# coreboards_mod001_rp2350_v01.net
KiCad netlist of a schematic drawn in EasyEDA Pro
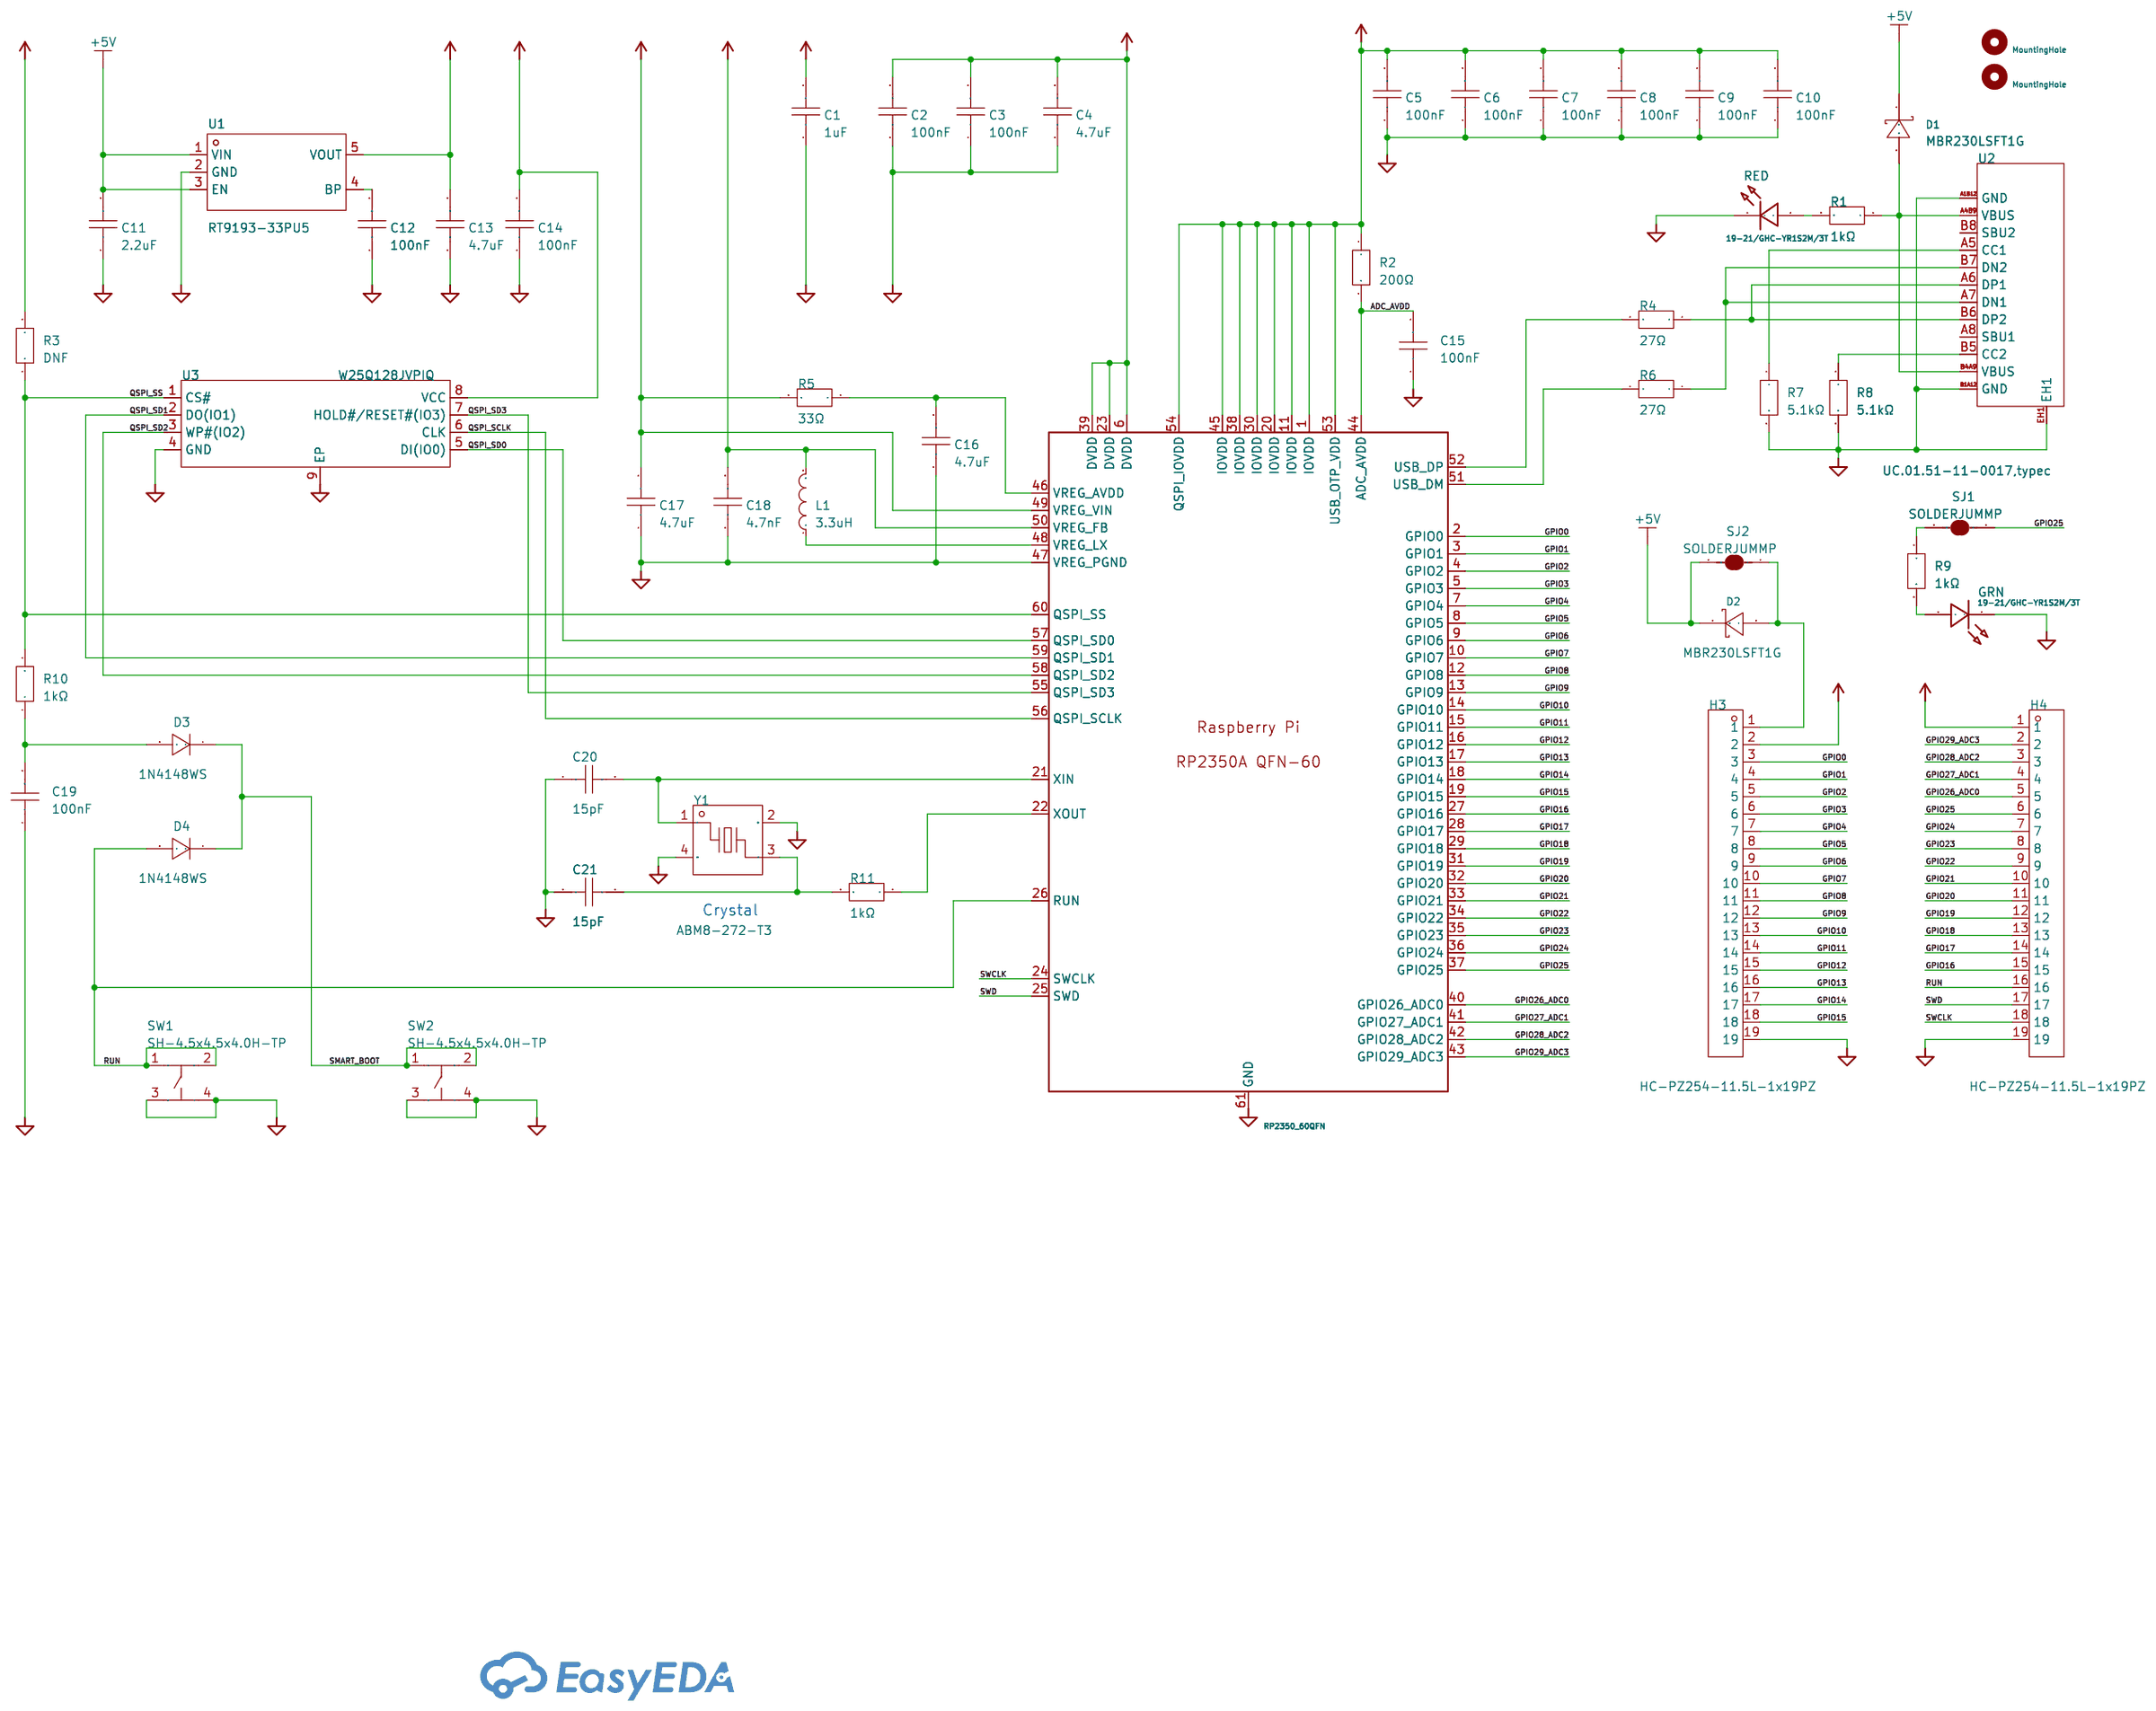
[diagram p0: schematic sheet]

(export (version "E")
  (design (tool "Eeschema 10.0.6"))
  (components
    (comp (ref "C1")
      (value "1uF")
      (footprint "easyedapro:C0603")
      (description "Capacitance:1nF Tolerance:±5% Tolerance:±5% Voltage Rating:200V Temperature Coefficient:C0G")
      (fields
        (field (name "Manufacturer Part") "C0603C102J2GECAUTO")
        (field (name "Manufacturer") "KEMET(基美)")
      )
      (libsource (lib "easyedapro") (part "C0603C102J2GECAUTO"))
    )
    (comp (ref "C2")
      (value "100nF")
      (footprint "easyedapro:C0603")
      (description "Capacitance:1nF Tolerance:±5% Tolerance:±5% Voltage Rating:200V Temperature Coefficient:C0G")
      (fields
        (field (name "Manufacturer Part") "C0603C102J2GECAUTO")
        (field (name "Manufacturer") "KEMET(基美)")
      )
      (libsource (lib "easyedapro") (part "C0603C102J2GECAUTO"))
    )
    (comp (ref "C3")
      (value "100nF")
      (footprint "easyedapro:C0603")
      (description "Capacitance:1nF Tolerance:±5% Tolerance:±5% Voltage Rating:200V Temperature Coefficient:C0G")
      (fields
        (field (name "Manufacturer Part") "C0603C102J2GECAUTO")
        (field (name "Manufacturer") "KEMET(基美)")
      )
      (libsource (lib "easyedapro") (part "C0603C102J2GECAUTO"))
    )
    (comp (ref "C4")
      (value "4.7uF")
      (footprint "easyedapro:C0603")
      (description "Capacitance:1nF Tolerance:±5% Tolerance:±5% Voltage Rating:200V Temperature Coefficient:C0G")
      (fields
        (field (name "Manufacturer Part") "C0603C102J2GECAUTO")
        (field (name "Manufacturer") "KEMET(基美)")
      )
      (libsource (lib "easyedapro") (part "C0603C102J2GECAUTO"))
    )
    (comp (ref "C5")
      (value "100nF")
      (footprint "easyedapro:C0603")
      (description "Capacitance:1nF Tolerance:±5% Tolerance:±5% Voltage Rating:200V Temperature Coefficient:C0G")
      (fields
        (field (name "Manufacturer Part") "C0603C102J2GECAUTO")
        (field (name "Manufacturer") "KEMET(基美)")
      )
      (libsource (lib "easyedapro") (part "C0603C102J2GECAUTO"))
    )
    (comp (ref "C6")
      (value "100nF")
      (footprint "easyedapro:C0603")
      (description "Capacitance:1nF Tolerance:±5% Tolerance:±5% Voltage Rating:200V Temperature Coefficient:C0G")
      (fields
        (field (name "Manufacturer Part") "C0603C102J2GECAUTO")
        (field (name "Manufacturer") "KEMET(基美)")
      )
      (libsource (lib "easyedapro") (part "C0603C102J2GECAUTO"))
    )
    (comp (ref "C7")
      (value "100nF")
      (footprint "easyedapro:C0603")
      (description "Capacitance:1nF Tolerance:±5% Tolerance:±5% Voltage Rating:200V Temperature Coefficient:C0G")
      (fields
        (field (name "Manufacturer Part") "C0603C102J2GECAUTO")
        (field (name "Manufacturer") "KEMET(基美)")
      )
      (libsource (lib "easyedapro") (part "C0603C102J2GECAUTO"))
    )
    (comp (ref "C8")
      (value "100nF")
      (footprint "easyedapro:C0603")
      (description "Capacitance:1nF Tolerance:±5% Tolerance:±5% Voltage Rating:200V Temperature Coefficient:C0G")
      (fields
        (field (name "Manufacturer Part") "C0603C102J2GECAUTO")
        (field (name "Manufacturer") "KEMET(基美)")
      )
      (libsource (lib "easyedapro") (part "C0603C102J2GECAUTO"))
    )
    (comp (ref "C9")
      (value "100nF")
      (footprint "easyedapro:C0603")
      (description "Capacitance:1nF Tolerance:±5% Tolerance:±5% Voltage Rating:200V Temperature Coefficient:C0G")
      (fields
        (field (name "Manufacturer Part") "C0603C102J2GECAUTO")
        (field (name "Manufacturer") "KEMET(基美)")
      )
      (libsource (lib "easyedapro") (part "C0603C102J2GECAUTO"))
    )
    (comp (ref "C10")
      (value "100nF")
      (footprint "easyedapro:C0603")
      (description "Capacitance:1nF Tolerance:±5% Tolerance:±5% Voltage Rating:200V Temperature Coefficient:C0G")
      (fields
        (field (name "Manufacturer Part") "C0603C102J2GECAUTO")
        (field (name "Manufacturer") "KEMET(基美)")
      )
      (libsource (lib "easyedapro") (part "C0603C102J2GECAUTO"))
    )
    (comp (ref "C11")
      (value "2.2uF")
      (footprint "easyedapro:C0603")
      (description "Capacitance:1nF Tolerance:±5% Tolerance:±5% Voltage Rating:200V Temperature Coefficient:C0G")
      (fields
        (field (name "Manufacturer Part") "C0603C102J2GECAUTO")
        (field (name "Manufacturer") "KEMET(基美)")
      )
      (libsource (lib "easyedapro") (part "C0603C102J2GECAUTO"))
    )
    (comp (ref "C12")
      (value "100nF")
      (footprint "easyedapro:C0603")
      (description "Capacitance:1nF Tolerance:±5% Tolerance:±5% Voltage Rating:200V Temperature Coefficient:C0G")
      (fields
        (field (name "Manufacturer Part") "C0603C102J2GECAUTO")
        (field (name "Manufacturer") "KEMET(基美)")
      )
      (libsource (lib "easyedapro") (part "C0603C102J2GECAUTO"))
    )
    (comp (ref "C13")
      (value "4.7uF")
      (footprint "easyedapro:C0603")
      (description "Capacitance:1nF Tolerance:±5% Tolerance:±5% Voltage Rating:200V Temperature Coefficient:C0G")
      (fields
        (field (name "Manufacturer Part") "C0603C102J2GECAUTO")
        (field (name "Manufacturer") "KEMET(基美)")
      )
      (libsource (lib "easyedapro") (part "C0603C102J2GECAUTO"))
    )
    (comp (ref "C14")
      (value "100nF")
      (footprint "easyedapro:C0603")
      (description "Capacitance:1nF Tolerance:±5% Tolerance:±5% Voltage Rating:200V Temperature Coefficient:C0G")
      (fields
        (field (name "Manufacturer Part") "C0603C102J2GECAUTO")
        (field (name "Manufacturer") "KEMET(基美)")
      )
      (libsource (lib "easyedapro") (part "C0603C102J2GECAUTO"))
    )
    (comp (ref "C15")
      (value "100nF")
      (footprint "easyedapro:C0603")
      (description "Capacitance:1nF Tolerance:±5% Tolerance:±5% Voltage Rating:200V Temperature Coefficient:C0G")
      (fields
        (field (name "Manufacturer Part") "C0603C102J2GECAUTO")
        (field (name "Manufacturer") "KEMET(基美)")
      )
      (libsource (lib "easyedapro") (part "C0603C102J2GECAUTO"))
    )
    (comp (ref "C16")
      (value "4.7uF")
      (footprint "easyedapro:C0603")
      (description "Capacitance:1nF Tolerance:±5% Tolerance:±5% Voltage Rating:200V Temperature Coefficient:C0G")
      (fields
        (field (name "Manufacturer Part") "C0603C102J2GECAUTO")
        (field (name "Manufacturer") "KEMET(基美)")
      )
      (libsource (lib "easyedapro") (part "C0603C102J2GECAUTO"))
    )
    (comp (ref "C17")
      (value "4.7uF")
      (footprint "easyedapro:C0603")
      (description "Capacitance:1nF Tolerance:±5% Tolerance:±5% Voltage Rating:200V Temperature Coefficient:C0G")
      (fields
        (field (name "Manufacturer Part") "C0603C102J2GECAUTO")
        (field (name "Manufacturer") "KEMET(基美)")
      )
      (libsource (lib "easyedapro") (part "C0603C102J2GECAUTO"))
    )
    (comp (ref "C18")
      (value "4.7nF")
      (footprint "easyedapro:C0603")
      (description "Capacitance:1nF Tolerance:±5% Tolerance:±5% Voltage Rating:200V Temperature Coefficient:C0G")
      (fields
        (field (name "Manufacturer Part") "C0603C102J2GECAUTO")
        (field (name "Manufacturer") "KEMET(基美)")
      )
      (libsource (lib "easyedapro") (part "C0603C102J2GECAUTO"))
    )
    (comp (ref "C19")
      (value "100nF")
      (footprint "easyedapro:C0603")
      (description "Capacitance:1nF Tolerance:±5% Tolerance:±5% Voltage Rating:200V Temperature Coefficient:C0G")
      (fields
        (field (name "Manufacturer Part") "C0603C102J2GECAUTO")
        (field (name "Manufacturer") "KEMET(基美)")
      )
      (libsource (lib "easyedapro") (part "C0603C102J2GECAUTO"))
    )
    (comp (ref "C20")
      (value "15pF")
      (footprint "easyedapro:C0603")
      (description "Capacitance:1nF Tolerance:±5% Tolerance:±5% Voltage Rating:200V Temperature Coefficient:C0G")
      (fields
        (field (name "Manufacturer Part") "C0603C102J2GECAUTO")
        (field (name "Manufacturer") "KEMET(基美)")
      )
      (libsource (lib "easyedapro") (part "C0603C102J2GECAUTO"))
    )
    (comp (ref "C21")
      (value "15pF")
      (footprint "easyedapro:C0603")
      (description "Capacitance:1nF Tolerance:±5% Tolerance:±5% Voltage Rating:200V Temperature Coefficient:C0G")
      (fields
        (field (name "Manufacturer Part") "C0603C102J2GECAUTO")
        (field (name "Manufacturer") "KEMET(基美)")
      )
      (libsource (lib "easyedapro") (part "C0603C102J2GECAUTO"))
    )
    (comp (ref "D1")
      (value "MBR230LSFT1G")
      (footprint "easyedapro:SOD-123FL_L2.7-W1.8-LS3.8-RD")
      (fields (field (name "Manufacturer") "onsemi(安森美)"))
      (libsource (lib "easyedapro") (part "MBR230LSFT1G"))
    )
    (comp (ref "D2")
      (value "MBR230LSFT1G")
      (footprint "easyedapro:SOD-123FL_L2.7-W1.8-LS3.8-RD")
      (fields (field (name "Manufacturer") "onsemi(安森美)"))
      (libsource (lib "easyedapro") (part "MBR230LSFT1G"))
    )
    (comp (ref "D3")
      (value "1N4148WS")
      (footprint "easyedapro:SOD-323_L1.8-W1.3-LS2.5-RD")
      (fields (field (name "Manufacturer") "CJ(江苏长电/长晶)"))
      (libsource (lib "easyedapro") (part "1N4148WS T4"))
    )
    (comp (ref "D4")
      (value "1N4148WS")
      (footprint "easyedapro:SOD-323_L1.8-W1.3-LS2.5-RD")
      (fields (field (name "Manufacturer") "CJ(江苏长电/长晶)"))
      (libsource (lib "easyedapro") (part "1N4148WS T4"))
    )
    (comp (ref "GRN")
      (value "19-21/GHC-YR1S2M/3T")
      (footprint "easyedapro:LED-SMD_L1.6-W0.8-RD")
      (fields (field (name "Manufacturer") "EVERLIGHT(亿光)") (field (name "Contributor") "LCSC"))
      (libsource (lib "easyedapro") (part "19-21/GHC-YR1S2M/3T"))
    )
    (comp (ref "H1")
      (value "MountingHole")
      (footprint "easyedapro:MountingHole:MountingHole_2.7mm_M2.5")
      (libsource (lib "easyedapro") (part "Mechanical_MountingHole"))
    )
    (comp (ref "H2")
      (value "MountingHole")
      (footprint "easyedapro:MountingHole:MountingHole_2.7mm_M2.5")
      (libsource (lib "easyedapro") (part "Mechanical_MountingHole"))
    )
    (comp (ref "H3")
      (value "HC-PZ254-11.5L-1x19PZ")
      (footprint "easyedapro:HDR-TH_19P-P2.54-V-M")
      (fields (field (name "Manufacturer") "HC(虹成电子)"))
      (libsource (lib "easyedapro") (part "HC-PZ254-11.5L-1X19PZ"))
    )
    (comp (ref "H4")
      (value "HC-PZ254-11.5L-1x19PZ")
      (footprint "easyedapro:HDR-TH_19P-P2.54-V-M")
      (fields (field (name "Manufacturer") "HC(虹成电子)"))
      (libsource (lib "easyedapro") (part "HC-PZ254-11.5L-1X19PZ"))
    )
    (comp (ref "L1")
      (value "3.3uH")
      (footprint "easyedapro:IND-SMD_L2.0-W1.6_AOTA-B201610S3R3-101-T")
      (fields
        (field (name "Manufacturer Part") "AOTA-B201610S3R3-101-T")
        (field (name "Manufacturer") "ABRACON")
      )
      (libsource (lib "easyedapro") (part "AOTA-B201610S3R3-101-T"))
    )
    (comp (ref "R1")
      (value "1kΩ")
      (footprint "easyedapro:R0603")
      (fields (field (name "Manufacturer Part") "RCC06031K50FKEA") (field (name "Manufacturer") "VISHAY(威世)"))
      (libsource (lib "easyedapro") (part "RCC06031K50FKEA"))
    )
    (comp (ref "R2")
      (value "200Ω")
      (footprint "easyedapro:R0603")
      (fields (field (name "Manufacturer Part") "RCC06031K50FKEA") (field (name "Manufacturer") "VISHAY(威世)"))
      (libsource (lib "easyedapro") (part "RCC06031K50FKEA"))
    )
    (comp (ref "R3")
      (value "DNF")
      (footprint "easyedapro:R0603")
      (fields (field (name "Manufacturer Part") "RCC06031K50FKEA") (field (name "Manufacturer") "VISHAY(威世)"))
      (libsource (lib "easyedapro") (part "RCC06031K50FKEA"))
    )
    (comp (ref "R4")
      (value "27Ω")
      (footprint "easyedapro:R0603")
      (fields (field (name "Manufacturer Part") "RCC06031K50FKEA") (field (name "Manufacturer") "VISHAY(威世)"))
      (libsource (lib "easyedapro") (part "RCC06031K50FKEA"))
    )
    (comp (ref "R5")
      (value "33Ω")
      (footprint "easyedapro:R0603")
      (fields (field (name "Manufacturer Part") "RCC06031K50FKEA") (field (name "Manufacturer") "VISHAY(威世)"))
      (libsource (lib "easyedapro") (part "RCC06031K50FKEA"))
    )
    (comp (ref "R6")
      (value "27Ω")
      (footprint "easyedapro:R0603")
      (fields (field (name "Manufacturer Part") "RCC06031K50FKEA") (field (name "Manufacturer") "VISHAY(威世)"))
      (libsource (lib "easyedapro") (part "RCC06031K50FKEA"))
    )
    (comp (ref "R7")
      (value "5.1kΩ")
      (footprint "easyedapro:R0603")
      (fields (field (name "Manufacturer Part") "RCC06031K50FKEA") (field (name "Manufacturer") "VISHAY(威世)"))
      (libsource (lib "easyedapro") (part "RCC06031K50FKEA"))
    )
    (comp (ref "R8")
      (value "5.1kΩ")
      (footprint "easyedapro:R0603")
      (fields (field (name "Manufacturer Part") "RCC06031K50FKEA") (field (name "Manufacturer") "VISHAY(威世)"))
      (libsource (lib "easyedapro") (part "RCC06031K50FKEA"))
    )
    (comp (ref "R9")
      (value "1kΩ")
      (footprint "easyedapro:R0603")
      (fields (field (name "Manufacturer Part") "RCC06031K50FKEA") (field (name "Manufacturer") "VISHAY(威世)"))
      (libsource (lib "easyedapro") (part "RCC06031K50FKEA"))
    )
    (comp (ref "R10")
      (value "1kΩ")
      (footprint "easyedapro:R0603")
      (fields (field (name "Manufacturer Part") "RCC06031K50FKEA") (field (name "Manufacturer") "VISHAY(威世)"))
      (libsource (lib "easyedapro") (part "RCC06031K50FKEA"))
    )
    (comp (ref "R11")
      (value "1kΩ")
      (footprint "easyedapro:R0603")
      (fields (field (name "Manufacturer Part") "RCC06031K50FKEA") (field (name "Manufacturer") "VISHAY(威世)"))
      (libsource (lib "easyedapro") (part "RCC06031K50FKEA"))
    )
    (comp (ref "RED")
      (value "19-21/GHC-YR1S2M/3T")
      (footprint "easyedapro:LED-SMD_L1.6-W0.8-RD")
      (fields (field (name "Manufacturer") "EVERLIGHT(亿光)") (field (name "Contributor") "LCSC"))
      (libsource (lib "easyedapro") (part "19-21/GHC-YR1S2M/3T"))
    )
    (comp (ref "SJ1")
      (value "SOLDERJUMMP")
      (footprint "easyedapro:SJ_2S-NO")
      (fields (field (name "Contributor") "SparkFun"))
      (libsource (lib "easyedapro") (part "SOLDERJUMPERNO"))
    )
    (comp (ref "SJ2")
      (value "SOLDERJUMMP")
      (footprint "easyedapro:SJ_2S-NO")
      (fields (field (name "Contributor") "SparkFun"))
      (libsource (lib "easyedapro") (part "SOLDERJUMPERNO"))
    )
    (comp (ref "SW1")
      (value "SH-4.5x4.5x4.0H-TP")
      (footprint "easyedapro:SW-SMD_4P-SH-4.5X4.5X4.0H-TP")
      (fields (field (name "Manufacturer") "SHOU HAN(首韩)"))
      (libsource (lib "easyedapro") (part "SH-4.5X4.5X4.0H-TP"))
    )
    (comp (ref "SW2")
      (value "SH-4.5x4.5x4.0H-TP")
      (footprint "easyedapro:SW-SMD_4P-SH-4.5X4.5X4.0H-TP")
      (fields (field (name "Manufacturer") "SHOU HAN(首韩)"))
      (libsource (lib "easyedapro") (part "SH-4.5X4.5X4.0H-TP"))
    )
    (comp (ref "U1")
      (value "RT9193-33PU5")
      (footprint "easyedapro:SC-70-5_L2.0-W1.3-P0.65-LS2.1-BL")
      (description "Output Type:-")
      (libsource (lib "easyedapro") (part "RT9193-33PU5"))
    )
    (comp (ref "U2")
      (value "UC.01.51-11-0017,typec")
      (footprint "easyedapro:TYPE-C-SMD_UC.01.51-11-0017")
      (libsource (lib "easyedapro") (part "UC.01.51-11-0017,TYPEC"))
    )
    (comp (ref "U3")
      (value "W25Q128JVPIQ")
      (footprint "easyedapro:WSON-8_L5.0-W6.0-P1.27-BL-EP")
      (fields (field (name "Manufacturer") "Winbond(华邦)"))
      (libsource (lib "easyedapro") (part "W25Q128JVPIQ"))
    )
    (comp (ref "U4")
      (value "RP2350_60QFN")
      (footprint "easyedapro:RP2350_60QFN_minimal:RP2350-QFN-60-1EP_7x7_P0.4mm_EP3.4x3.4mm_ThermalVias")
      (libsource (lib "easyedapro") (part "MCU_RaspberryPi_RP2350_RP2350_60QFN"))
    )
    (comp (ref "Y1")
      (value "ABM8-272-T3")
      (footprint "easyedapro:CRYSTAL-SMD_4P-L3.2-W2.5-BL-2")
      (libsource (lib "easyedapro") (part "ABM8-272-T3"))
    )
  )
  (nets
    (net (code "1") (name "+5V") (class "Default")
      (node (ref "C11") (pin "2") (pinfunction "2_2") (pintype "unspecified"))
      (node (ref "D1") (pin "1") (pinfunction "C_1") (pintype "input"))
      (node (ref "D2") (pin "1") (pinfunction "C_1") (pintype "input"))
      (node (ref "SJ2") (pin "2") (pinfunction "2_2") (pintype "unspecified"))
      (node (ref "U1") (pin "1") (pinfunction "VIN_1") (pintype "unspecified"))
      (node (ref "U1") (pin "3") (pinfunction "EN_3") (pintype "unspecified"))
    )
    (net (code "2") (name "/ADC_AVDD") (class "Default")
      (node (ref "C15") (pin "2") (pinfunction "2_2") (pintype "unspecified"))
      (node (ref "R2") (pin "2") (pinfunction "2_2") (pintype "unspecified"))
      (node (ref "U4") (pin "44") (pinfunction "ADC_AVDD_44") (pintype "unspecified"))
    )
    (net (code "3") (name "/GPIO0") (class "Default")
      (node (ref "H3") (pin "3") (pinfunction "3_3") (pintype "unspecified"))
      (node (ref "U4") (pin "2") (pinfunction "GPIO0_2") (pintype "bidirectional"))
    )
    (net (code "4") (name "/GPIO1") (class "Default")
      (node (ref "H3") (pin "4") (pinfunction "4_4") (pintype "unspecified"))
      (node (ref "U4") (pin "3") (pinfunction "GPIO1_3") (pintype "bidirectional"))
    )
    (net (code "5") (name "/GPIO2") (class "Default")
      (node (ref "H3") (pin "5") (pinfunction "5_5") (pintype "unspecified"))
      (node (ref "U4") (pin "4") (pinfunction "GPIO2_4") (pintype "bidirectional"))
    )
    (net (code "6") (name "/GPIO3") (class "Default")
      (node (ref "H3") (pin "6") (pinfunction "6_6") (pintype "unspecified"))
      (node (ref "U4") (pin "5") (pinfunction "GPIO3_5") (pintype "bidirectional"))
    )
    (net (code "7") (name "/GPIO4") (class "Default")
      (node (ref "H3") (pin "7") (pinfunction "7_7") (pintype "unspecified"))
      (node (ref "U4") (pin "7") (pinfunction "GPIO4_7") (pintype "bidirectional"))
    )
    (net (code "8") (name "/GPIO5") (class "Default")
      (node (ref "H3") (pin "8") (pinfunction "8_8") (pintype "unspecified"))
      (node (ref "U4") (pin "8") (pinfunction "GPIO5_8") (pintype "bidirectional"))
    )
    (net (code "9") (name "/GPIO6") (class "Default")
      (node (ref "H3") (pin "9") (pinfunction "9_9") (pintype "unspecified"))
      (node (ref "U4") (pin "9") (pinfunction "GPIO6_9") (pintype "bidirectional"))
    )
    (net (code "10") (name "/GPIO7") (class "Default")
      (node (ref "H3") (pin "10") (pinfunction "10_10") (pintype "unspecified"))
      (node (ref "U4") (pin "10") (pinfunction "GPIO7_10") (pintype "bidirectional"))
    )
    (net (code "11") (name "/GPIO8") (class "Default")
      (node (ref "H3") (pin "11") (pinfunction "11_11") (pintype "unspecified"))
      (node (ref "U4") (pin "12") (pinfunction "GPIO8_12") (pintype "bidirectional"))
    )
    (net (code "12") (name "/GPIO9") (class "Default")
      (node (ref "H3") (pin "12") (pinfunction "12_12") (pintype "unspecified"))
      (node (ref "U4") (pin "13") (pinfunction "GPIO9_13") (pintype "bidirectional"))
    )
    (net (code "13") (name "/GPIO10") (class "Default")
      (node (ref "H3") (pin "13") (pinfunction "13_13") (pintype "unspecified"))
      (node (ref "U4") (pin "14") (pinfunction "GPIO10_14") (pintype "bidirectional"))
    )
    (net (code "14") (name "/GPIO11") (class "Default")
      (node (ref "H3") (pin "14") (pinfunction "14_14") (pintype "unspecified"))
      (node (ref "U4") (pin "15") (pinfunction "GPIO11_15") (pintype "bidirectional"))
    )
    (net (code "15") (name "/GPIO12") (class "Default")
      (node (ref "H3") (pin "15") (pinfunction "15_15") (pintype "unspecified"))
      (node (ref "U4") (pin "16") (pinfunction "GPIO12_16") (pintype "bidirectional"))
    )
    (net (code "16") (name "/GPIO13") (class "Default")
      (node (ref "H3") (pin "16") (pinfunction "16_16") (pintype "unspecified"))
      (node (ref "U4") (pin "17") (pinfunction "GPIO13_17") (pintype "bidirectional"))
    )
    (net (code "17") (name "/GPIO14") (class "Default")
      (node (ref "H3") (pin "17") (pinfunction "17_17") (pintype "unspecified"))
      (node (ref "U4") (pin "18") (pinfunction "GPIO14_18") (pintype "bidirectional"))
    )
    (net (code "18") (name "/GPIO15") (class "Default")
      (node (ref "H3") (pin "18") (pinfunction "18_18") (pintype "unspecified"))
      (node (ref "U4") (pin "19") (pinfunction "GPIO15_19") (pintype "bidirectional"))
    )
    (net (code "19") (name "/GPIO16") (class "Default")
      (node (ref "H4") (pin "15") (pinfunction "15_15") (pintype "unspecified"))
      (node (ref "U4") (pin "27") (pinfunction "GPIO16_27") (pintype "bidirectional"))
    )
    (net (code "20") (name "/GPIO17") (class "Default")
      (node (ref "H4") (pin "14") (pinfunction "14_14") (pintype "unspecified"))
      (node (ref "U4") (pin "28") (pinfunction "GPIO17_28") (pintype "bidirectional"))
    )
    (net (code "21") (name "/GPIO18") (class "Default")
      (node (ref "H4") (pin "13") (pinfunction "13_13") (pintype "unspecified"))
      (node (ref "U4") (pin "29") (pinfunction "GPIO18_29") (pintype "bidirectional"))
    )
    (net (code "22") (name "/GPIO19") (class "Default")
      (node (ref "H4") (pin "12") (pinfunction "12_12") (pintype "unspecified"))
      (node (ref "U4") (pin "31") (pinfunction "GPIO19_31") (pintype "bidirectional"))
    )
    (net (code "23") (name "/GPIO20") (class "Default")
      (node (ref "H4") (pin "11") (pinfunction "11_11") (pintype "unspecified"))
      (node (ref "U4") (pin "32") (pinfunction "GPIO20_32") (pintype "bidirectional"))
    )
    (net (code "24") (name "/GPIO21") (class "Default")
      (node (ref "H4") (pin "10") (pinfunction "10_10") (pintype "unspecified"))
      (node (ref "U4") (pin "33") (pinfunction "GPIO21_33") (pintype "bidirectional"))
    )
    (net (code "25") (name "/GPIO22") (class "Default")
      (node (ref "H4") (pin "9") (pinfunction "9_9") (pintype "unspecified"))
      (node (ref "U4") (pin "34") (pinfunction "GPIO22_34") (pintype "bidirectional"))
    )
    (net (code "26") (name "/GPIO23") (class "Default")
      (node (ref "H4") (pin "8") (pinfunction "8_8") (pintype "unspecified"))
      (node (ref "U4") (pin "35") (pinfunction "GPIO23_35") (pintype "bidirectional"))
    )
    (net (code "27") (name "/GPIO24") (class "Default")
      (node (ref "H4") (pin "7") (pinfunction "7_7") (pintype "unspecified"))
      (node (ref "U4") (pin "36") (pinfunction "GPIO24_36") (pintype "bidirectional"))
    )
    (net (code "28") (name "/GPIO25") (class "Default")
      (node (ref "H4") (pin "6") (pinfunction "6_6") (pintype "unspecified"))
      (node (ref "SJ1") (pin "1") (pinfunction "1_1") (pintype "unspecified"))
      (node (ref "U4") (pin "37") (pinfunction "GPIO25_37") (pintype "bidirectional"))
    )
    (net (code "29") (name "/GPIO26_ADC0") (class "Default")
      (node (ref "H4") (pin "5") (pinfunction "5_5") (pintype "unspecified"))
      (node (ref "U4") (pin "40") (pinfunction "GPIO26_ADC0_40") (pintype "bidirectional"))
    )
    (net (code "30") (name "/GPIO27_ADC1") (class "Default")
      (node (ref "H4") (pin "4") (pinfunction "4_4") (pintype "unspecified"))
      (node (ref "U4") (pin "41") (pinfunction "GPIO27_ADC1_41") (pintype "bidirectional"))
    )
    (net (code "31") (name "/GPIO28_ADC2") (class "Default")
      (node (ref "H4") (pin "3") (pinfunction "3_3") (pintype "unspecified"))
      (node (ref "U4") (pin "42") (pinfunction "GPIO28_ADC2_42") (pintype "bidirectional"))
    )
    (net (code "32") (name "/GPIO29_ADC3") (class "Default")
      (node (ref "H4") (pin "2") (pinfunction "2_2") (pintype "unspecified"))
      (node (ref "U4") (pin "43") (pinfunction "GPIO29_ADC3_43") (pintype "bidirectional"))
    )
    (net (code "33") (name "/QSPI_SCLK") (class "Default")
      (node (ref "U3") (pin "6") (pinfunction "CLK_6") (pintype "unspecified"))
      (node (ref "U4") (pin "56") (pinfunction "QSPI_SCLK_56") (pintype "output"))
    )
    (net (code "34") (name "/QSPI_SD0") (class "Default")
      (node (ref "U3") (pin "5") (pinfunction "DI(IO0)_5") (pintype "unspecified"))
      (node (ref "U4") (pin "57") (pinfunction "QSPI_SD0_57") (pintype "bidirectional"))
    )
    (net (code "35") (name "/QSPI_SD1") (class "Default")
      (node (ref "U3") (pin "2") (pinfunction "DO(IO1)_2") (pintype "unspecified"))
      (node (ref "U4") (pin "59") (pinfunction "QSPI_SD1_59") (pintype "bidirectional"))
    )
    (net (code "36") (name "/QSPI_SD2") (class "Default")
      (node (ref "U3") (pin "3") (pinfunction "WP#(IO2)_3") (pintype "unspecified"))
      (node (ref "U4") (pin "58") (pinfunction "QSPI_SD2_58") (pintype "bidirectional"))
    )
    (net (code "37") (name "/QSPI_SD3") (class "Default")
      (node (ref "U3") (pin "7") (pinfunction "HOLD#/RESET#(IO3)_7") (pintype "unspecified"))
      (node (ref "U4") (pin "55") (pinfunction "QSPI_SD3_55") (pintype "bidirectional"))
    )
    (net (code "38") (name "/QSPI_SS") (class "Default")
      (node (ref "R10") (pin "2") (pinfunction "2_2") (pintype "unspecified"))
      (node (ref "R3") (pin "1") (pinfunction "1_1") (pintype "unspecified"))
      (node (ref "U3") (pin "1") (pinfunction "CS#_1") (pintype "unspecified"))
      (node (ref "U4") (pin "60") (pinfunction "QSPI_SS_60") (pintype "bidirectional"))
    )
    (net (code "39") (name "/RUN") (class "Default")
      (node (ref "D4") (pin "2") (pinfunction "A_2") (pintype "unspecified"))
      (node (ref "H4") (pin "16") (pinfunction "16_16") (pintype "unspecified"))
      (node (ref "SW1") (pin "1") (pinfunction "1_1") (pintype "unspecified"))
      (node (ref "SW1") (pin "2") (pinfunction "2_2") (pintype "unspecified"))
      (node (ref "U4") (pin "26") (pinfunction "RUN_26") (pintype "input"))
    )
    (net (code "40") (name "/SMART_BOOT") (class "Default")
      (node (ref "D3") (pin "1") (pinfunction "K_1") (pintype "unspecified"))
      (node (ref "D4") (pin "1") (pinfunction "K_1") (pintype "unspecified"))
      (node (ref "SW2") (pin "1") (pinfunction "1_1") (pintype "unspecified"))
      (node (ref "SW2") (pin "2") (pinfunction "2_2") (pintype "unspecified"))
    )
    (net (code "41") (name "/SWCLK") (class "Default")
      (node (ref "H4") (pin "18") (pinfunction "18_18") (pintype "unspecified"))
      (node (ref "U4") (pin "24") (pinfunction "SWCLK_24") (pintype "output"))
    )
    (net (code "42") (name "/SWD") (class "Default")
      (node (ref "H4") (pin "17") (pinfunction "17_17") (pintype "unspecified"))
      (node (ref "U4") (pin "25") (pinfunction "SWD_25") (pintype "bidirectional"))
    )
    (net (code "43") (name "Net-(C21-Pad2)") (class "Default")
      (node (ref "C21") (pin "2") (pinfunction "2_2") (pintype "unspecified"))
      (node (ref "R11") (pin "2") (pinfunction "2_2") (pintype "unspecified"))
      (node (ref "Y1") (pin "3") (pinfunction "3_3") (pintype "input"))
    )
    (net (code "44") (name "Net-(D1-A)") (class "Default")
      (node (ref "D1") (pin "2") (pinfunction "A_2") (pintype "input"))
      (node (ref "R1") (pin "1") (pinfunction "1_1") (pintype "unspecified"))
      (node (ref "U2") (pin "A4B9") (pinfunction "VBUS_A4B9") (pintype "unspecified"))
      (node (ref "U2") (pin "B4A9") (pinfunction "VBUS_B4A9") (pintype "unspecified"))
    )
    (net (code "45") (name "Net-(D2-A)") (class "Default")
      (node (ref "D2") (pin "2") (pinfunction "A_2") (pintype "input"))
      (node (ref "H3") (pin "1") (pinfunction "1_1") (pintype "unspecified"))
      (node (ref "SJ2") (pin "1") (pinfunction "1_1") (pintype "unspecified"))
    )
    (net (code "46") (name "Net-(D3-A)") (class "Default")
      (node (ref "C19") (pin "2") (pinfunction "2_2") (pintype "unspecified"))
      (node (ref "D3") (pin "2") (pinfunction "A_2") (pintype "unspecified"))
      (node (ref "R10") (pin "1") (pinfunction "1_1") (pintype "unspecified"))
    )
    (net (code "47") (name "Net-(GRN-+)") (class "Default")
      (node (ref "GRN") (pin "2") (pinfunction "+_2") (pintype "unspecified"))
      (node (ref "R9") (pin "2") (pinfunction "2_2") (pintype "unspecified"))
    )
    (net (code "48") (name "Net-(R9-Pad1)") (class "Default")
      (node (ref "R9") (pin "1") (pinfunction "1_1") (pintype "unspecified"))
      (node (ref "SJ1") (pin "2") (pinfunction "2_2") (pintype "unspecified"))
    )
    (net (code "49") (name "Net-(RED-+)") (class "Default")
      (node (ref "R1") (pin "2") (pinfunction "2_2") (pintype "unspecified"))
      (node (ref "RED") (pin "2") (pinfunction "+_2") (pintype "unspecified"))
    )
    (net (code "50") (name "Net-(U1-BP)") (class "Default")
      (node (ref "C12") (pin "2") (pinfunction "2_2") (pintype "unspecified"))
      (node (ref "U1") (pin "4") (pinfunction "BP_4") (pintype "unspecified"))
    )
    (net (code "51") (name "Net-(U2-CC1)") (class "Default")
      (node (ref "R7") (pin "1") (pinfunction "1_1") (pintype "unspecified"))
      (node (ref "U2") (pin "A5") (pinfunction "CC1_A5") (pintype "unspecified"))
    )
    (net (code "52") (name "Net-(U2-CC2)") (class "Default")
      (node (ref "R8") (pin "1") (pinfunction "1_1") (pintype "unspecified"))
      (node (ref "U2") (pin "B5") (pinfunction "CC2_B5") (pintype "unspecified"))
    )
    (net (code "53") (name "Net-(U2-DN1)") (class "Default")
      (node (ref "R6") (pin "1") (pinfunction "1_1") (pintype "unspecified"))
      (node (ref "U2") (pin "A7") (pinfunction "DN1_A7") (pintype "unspecified"))
      (node (ref "U2") (pin "B7") (pinfunction "DN2_B7") (pintype "unspecified"))
    )
    (net (code "54") (name "Net-(U2-DP1)") (class "Default")
      (node (ref "R4") (pin "1") (pinfunction "1_1") (pintype "unspecified"))
      (node (ref "U2") (pin "A6") (pinfunction "DP1_A6") (pintype "unspecified"))
      (node (ref "U2") (pin "B6") (pinfunction "DP2_B6") (pintype "unspecified"))
    )
    (net (code "55") (name "Net-(U4-USB_DM)") (class "Default")
      (node (ref "R6") (pin "2") (pinfunction "2_2") (pintype "unspecified"))
      (node (ref "U4") (pin "51") (pinfunction "USB_DM_51") (pintype "bidirectional"))
    )
    (net (code "56") (name "Net-(U4-USB_DP)") (class "Default")
      (node (ref "R4") (pin "2") (pinfunction "2_2") (pintype "unspecified"))
      (node (ref "U4") (pin "52") (pinfunction "USB_DP_52") (pintype "bidirectional"))
    )
    (net (code "57") (name "Net-(U4-VREG_AVDD)") (class "Default")
      (node (ref "C16") (pin "2") (pinfunction "2_2") (pintype "unspecified"))
      (node (ref "R5") (pin "1") (pinfunction "1_1") (pintype "unspecified"))
      (node (ref "U4") (pin "46") (pinfunction "VREG_AVDD_46") (pintype "unspecified"))
    )
    (net (code "58") (name "Net-(U4-VREG_LX)") (class "Default")
      (node (ref "L1") (pin "1") (pinfunction "1_1") (pintype "unspecified"))
      (node (ref "U4") (pin "48") (pinfunction "VREG_LX_48") (pintype "unspecified"))
    )
    (net (code "59") (name "Net-(U4-XIN)") (class "Default")
      (node (ref "C20") (pin "2") (pinfunction "2_2") (pintype "unspecified"))
      (node (ref "U4") (pin "21") (pinfunction "XIN_21") (pintype "input"))
      (node (ref "Y1") (pin "1") (pinfunction "1_1") (pintype "input"))
    )
    (net (code "60") (name "Net-(U4-XOUT)") (class "Default")
      (node (ref "R11") (pin "1") (pinfunction "1_1") (pintype "unspecified"))
      (node (ref "U4") (pin "22") (pinfunction "XOUT_22") (pintype "unspecified"))
    )
    (net (code "61") (name "POWER_+1V1") (class "Default")
      (node (ref "C18") (pin "2") (pinfunction "2_2") (pintype "unspecified"))
      (node (ref "C2") (pin "2") (pinfunction "2_2") (pintype "unspecified"))
      (node (ref "C3") (pin "2") (pinfunction "2_2") (pintype "unspecified"))
      (node (ref "C4") (pin "2") (pinfunction "2_2") (pintype "unspecified"))
      (node (ref "L1") (pin "2") (pinfunction "2_2") (pintype "unspecified"))
      (node (ref "U4") (pin "23") (pinfunction "DVDD_23") (pintype "unspecified"))
      (node (ref "U4") (pin "39") (pinfunction "DVDD_39") (pintype "unspecified"))
      (node (ref "U4") (pin "50") (pinfunction "VREG_FB_50") (pintype "input"))
      (node (ref "U4") (pin "6") (pinfunction "DVDD_6") (pintype "unspecified"))
    )
    (net (code "62") (name "POWER_+3V3") (class "Default")
      (node (ref "C1") (pin "2") (pinfunction "2_2") (pintype "unspecified"))
      (node (ref "C10") (pin "2") (pinfunction "2_2") (pintype "unspecified"))
      (node (ref "C13") (pin "2") (pinfunction "2_2") (pintype "unspecified"))
      (node (ref "C14") (pin "2") (pinfunction "2_2") (pintype "unspecified"))
      (node (ref "C17") (pin "2") (pinfunction "2_2") (pintype "unspecified"))
      (node (ref "C5") (pin "2") (pinfunction "2_2") (pintype "unspecified"))
      (node (ref "C6") (pin "2") (pinfunction "2_2") (pintype "unspecified"))
      (node (ref "C7") (pin "2") (pinfunction "2_2") (pintype "unspecified"))
      (node (ref "C8") (pin "2") (pinfunction "2_2") (pintype "unspecified"))
      (node (ref "C9") (pin "2") (pinfunction "2_2") (pintype "unspecified"))
      (node (ref "H3") (pin "2") (pinfunction "2_2") (pintype "unspecified"))
      (node (ref "H4") (pin "1") (pinfunction "1_1") (pintype "unspecified"))
      (node (ref "R2") (pin "1") (pinfunction "1_1") (pintype "unspecified"))
      (node (ref "R3") (pin "2") (pinfunction "2_2") (pintype "unspecified"))
      (node (ref "R5") (pin "2") (pinfunction "2_2") (pintype "unspecified"))
      (node (ref "U1") (pin "5") (pinfunction "VOUT_5") (pintype "unspecified"))
      (node (ref "U3") (pin "8") (pinfunction "VCC_8") (pintype "unspecified"))
      (node (ref "U4") (pin "1") (pinfunction "IOVDD_1") (pintype "unspecified"))
      (node (ref "U4") (pin "11") (pinfunction "IOVDD_11") (pintype "unspecified"))
      (node (ref "U4") (pin "20") (pinfunction "IOVDD_20") (pintype "unspecified"))
      (node (ref "U4") (pin "30") (pinfunction "IOVDD_30") (pintype "unspecified"))
      (node (ref "U4") (pin "38") (pinfunction "IOVDD_38") (pintype "unspecified"))
      (node (ref "U4") (pin "45") (pinfunction "IOVDD_45") (pintype "unspecified"))
      (node (ref "U4") (pin "49") (pinfunction "VREG_VIN_49") (pintype "unspecified"))
      (node (ref "U4") (pin "53") (pinfunction "USB_OTP_VDD_53") (pintype "unspecified"))
      (node (ref "U4") (pin "54") (pinfunction "QSPI_IOVDD_54") (pintype "unspecified"))
    )
    (net (code "63") (name "POWER_GND") (class "Default")
      (node (ref "C1") (pin "1") (pinfunction "1_1") (pintype "unspecified"))
      (node (ref "C10") (pin "1") (pinfunction "1_1") (pintype "unspecified"))
      (node (ref "C11") (pin "1") (pinfunction "1_1") (pintype "unspecified"))
      (node (ref "C12") (pin "1") (pinfunction "1_1") (pintype "unspecified"))
      (node (ref "C13") (pin "1") (pinfunction "1_1") (pintype "unspecified"))
      (node (ref "C14") (pin "1") (pinfunction "1_1") (pintype "unspecified"))
      (node (ref "C15") (pin "1") (pinfunction "1_1") (pintype "unspecified"))
      (node (ref "C16") (pin "1") (pinfunction "1_1") (pintype "unspecified"))
      (node (ref "C17") (pin "1") (pinfunction "1_1") (pintype "unspecified"))
      (node (ref "C18") (pin "1") (pinfunction "1_1") (pintype "unspecified"))
      (node (ref "C19") (pin "1") (pinfunction "1_1") (pintype "unspecified"))
      (node (ref "C2") (pin "1") (pinfunction "1_1") (pintype "unspecified"))
      (node (ref "C20") (pin "1") (pinfunction "1_1") (pintype "unspecified"))
      (node (ref "C21") (pin "1") (pinfunction "1_1") (pintype "unspecified"))
      (node (ref "C3") (pin "1") (pinfunction "1_1") (pintype "unspecified"))
      (node (ref "C4") (pin "1") (pinfunction "1_1") (pintype "unspecified"))
      (node (ref "C5") (pin "1") (pinfunction "1_1") (pintype "unspecified"))
      (node (ref "C6") (pin "1") (pinfunction "1_1") (pintype "unspecified"))
      (node (ref "C7") (pin "1") (pinfunction "1_1") (pintype "unspecified"))
      (node (ref "C8") (pin "1") (pinfunction "1_1") (pintype "unspecified"))
      (node (ref "C9") (pin "1") (pinfunction "1_1") (pintype "unspecified"))
      (node (ref "GRN") (pin "1") (pinfunction "-_1") (pintype "unspecified"))
      (node (ref "H3") (pin "19") (pinfunction "19_19") (pintype "unspecified"))
      (node (ref "H4") (pin "19") (pinfunction "19_19") (pintype "unspecified"))
      (node (ref "R7") (pin "2") (pinfunction "2_2") (pintype "unspecified"))
      (node (ref "R8") (pin "2") (pinfunction "2_2") (pintype "unspecified"))
      (node (ref "RED") (pin "1") (pinfunction "-_1") (pintype "unspecified"))
      (node (ref "SW1") (pin "3") (pinfunction "3_3") (pintype "unspecified"))
      (node (ref "SW1") (pin "4") (pinfunction "4_4") (pintype "unspecified"))
      (node (ref "SW2") (pin "3") (pinfunction "3_3") (pintype "unspecified"))
      (node (ref "SW2") (pin "4") (pinfunction "4_4") (pintype "unspecified"))
      (node (ref "U1") (pin "2") (pinfunction "GND_2") (pintype "unspecified"))
      (node (ref "U2") (pin "A1B12") (pinfunction "GND_A1B12") (pintype "unspecified"))
      (node (ref "U2") (pin "B1A12") (pinfunction "GND_B1A12") (pintype "unspecified"))
      (node (ref "U2") (pin "EH1") (pinfunction "EH1_EH1") (pintype "unspecified"))
      (node (ref "U3") (pin "4") (pinfunction "GND_4") (pintype "unspecified"))
      (node (ref "U3") (pin "9") (pinfunction "EP_9") (pintype "unspecified"))
      (node (ref "U4") (pin "47") (pinfunction "VREG_PGND_47") (pintype "unspecified"))
      (node (ref "U4") (pin "61") (pinfunction "GND_61") (pintype "unspecified"))
      (node (ref "Y1") (pin "2") (pinfunction "GND_2") (pintype "input"))
      (node (ref "Y1") (pin "4") (pinfunction "GND_4") (pintype "input"))
    )
    (net (code "64") (name "unconnected-(U2-SBU1-PadA8)") (class "Default")
      (node (ref "U2") (pin "A8") (pinfunction "SBU1_A8") (pintype "unspecified"))
    )
    (net (code "65") (name "unconnected-(U2-SBU2-PadB8)") (class "Default")
      (node (ref "U2") (pin "B8") (pinfunction "SBU2_B8") (pintype "unspecified"))
    )
  )
)
